# DS158-1_0-B.net
KiCad netlist of a schematic drawn in Altium Designer
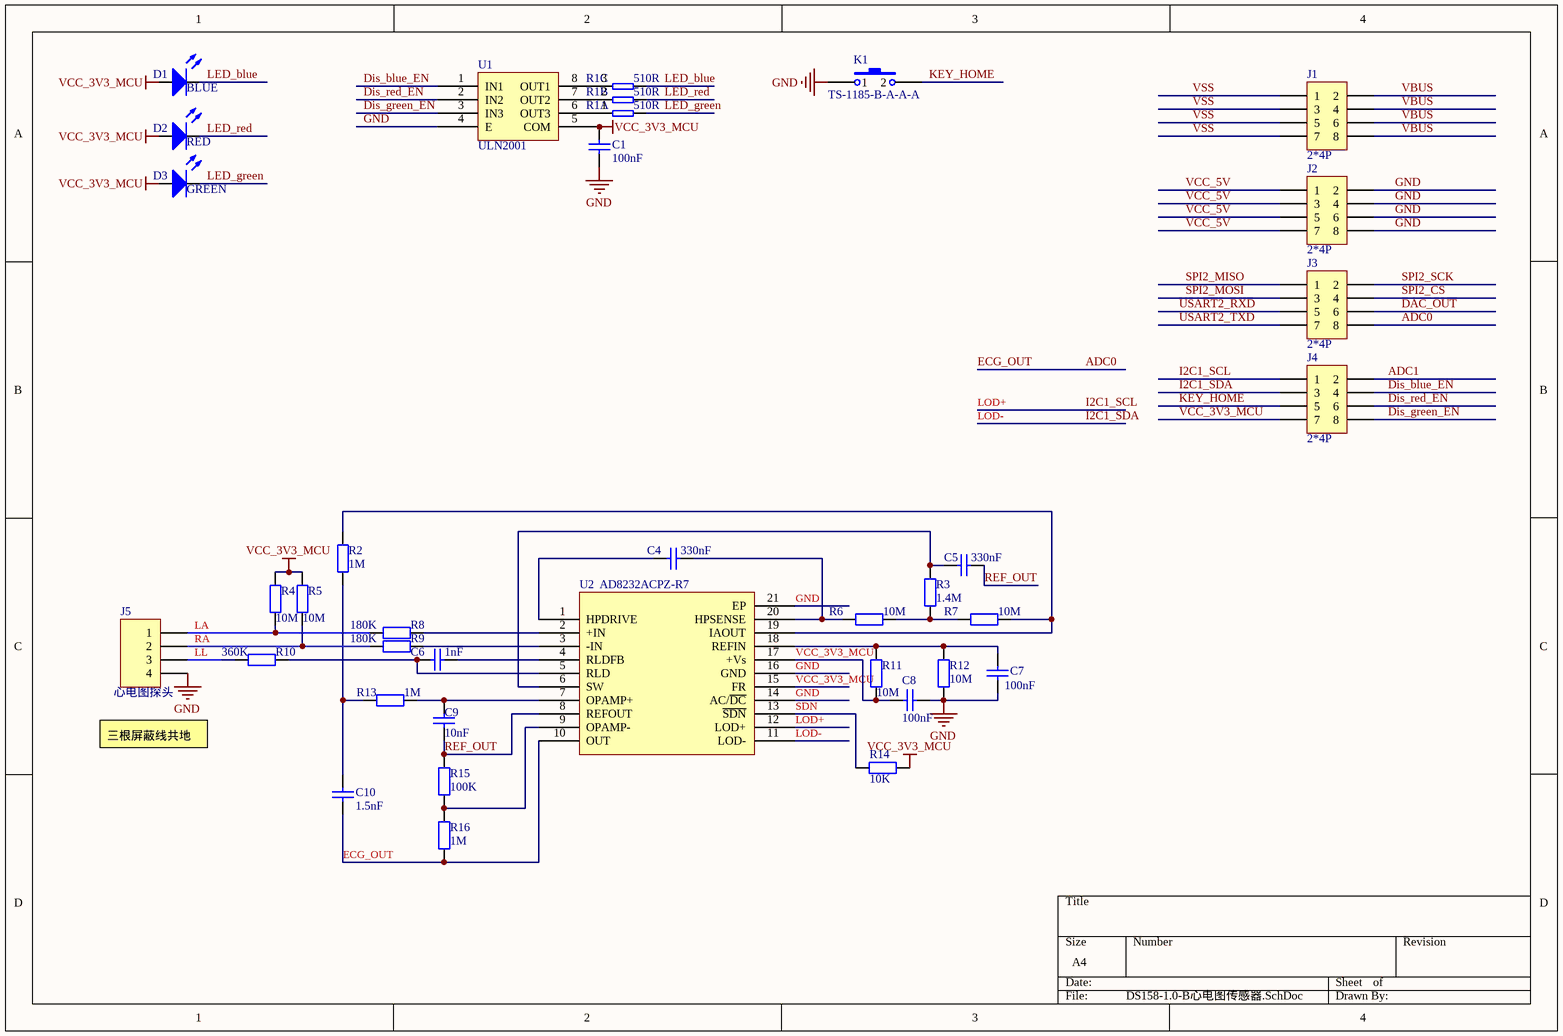
[diagram p0: DS158-1.0-B心电图传感器.SchDoc]

(export (version "E")
  (design (tool "Eeschema 10.0.6"))
  (components
    (comp (ref "C1")
      (value "100nF")
      (footprint "0603CAP")
      (description "贴片电容")
      (fields (field (name "Comment") "SMDCAP00013"))
      (libsource (lib "AD_SCH") (part "MLCC 100nF 50V ±10％ 0603"))
    )
    (comp (ref "C4")
      (value "330nF")
      (footprint "0603CAP")
      (description "贴片电容")
      (fields (field (name "Comment") "MLCC 330nF 50V ±5％ 0603"))
      (libsource (lib "AD_SCH") (part "MLCC 330nF 50V ±5％ 0603"))
    )
    (comp (ref "C5")
      (value "330nF")
      (footprint "0603CAP")
      (description "贴片电容")
      (fields (field (name "Comment") "MLCC 330nF 50V ±5％ 0603"))
      (libsource (lib "AD_SCH") (part "MLCC 330nF 50V ±5％ 0603"))
    )
    (comp (ref "C6")
      (value "1nF")
      (footprint "0603CAP")
      (description "贴片电容")
      (fields (field (name "Comment") "SMDCAP00008"))
      (libsource (lib "AD_SCH") (part "MLCC 1nF 50V ±10％ 0603"))
    )
    (comp (ref "C7")
      (value "100nF")
      (footprint "0603CAP")
      (description "贴片电容")
      (fields (field (name "Comment") "SMDCAP00013"))
      (libsource (lib "AD_SCH") (part "MLCC 100nF 50V ±10％ 0603"))
    )
    (comp (ref "C8")
      (value "100nF")
      (footprint "0603CAP")
      (description "贴片电容")
      (fields (field (name "Comment") "SMDCAP00013"))
      (libsource (lib "AD_SCH") (part "MLCC 100nF 50V ±10％ 0603"))
    )
    (comp (ref "C9")
      (value "10nF")
      (footprint "0603CAP")
      (description "贴片电容")
      (fields (field (name "Comment") "SMDCAP00010"))
      (libsource (lib "AD_SCH") (part "MLCC 10nF 50V ±10％ 0603"))
    )
    (comp (ref "C10")
      (value "1.5nF")
      (footprint "0603CAP")
      (description "贴片电容")
      (fields (field (name "Comment") "SMDCAP00008"))
      (libsource (lib "AD_SCH") (part "MLCC 1.5nF 50V ±10％ 0603"))
    )
    (comp (ref "D1")
      (value "BLUE")
      (footprint "LED_0805")
      (description "贴片LED")
      (fields (field (name "Comment") "SMDLED00010"))
      (libsource (lib "AD_SCH") (part "Chip 蓝色LED 0805"))
    )
    (comp (ref "D2")
      (value "RED")
      (footprint "LED_0805")
      (description "贴片LED")
      (fields (field (name "Comment") "SMDLED00003"))
      (libsource (lib "AD_SCH") (part "Chip 红色LED 0805"))
    )
    (comp (ref "D3")
      (value "GREEN")
      (footprint "LED_0805")
      (description "贴片LED")
      (fields (field (name "Comment") "Chip 翠绿LED 0805"))
      (libsource (lib "AD_SCH") (part "Chip 翠绿LED 0805"))
    )
    (comp (ref "J1")
      (value "2*4P")
      (footprint "X1321WVS-2x04J-C40D53")
      (description "双排针2x4P 立贴 1.27mm")
      (fields (field (name "Comment") "X1321WVS-2x04J-C40D53"))
      (libsource (lib "AD_SCH") (part "X1321WVS-2x04J-C40D53"))
    )
    (comp (ref "J2")
      (value "2*4P")
      (footprint "X1321WVS-2x04J-C40D53")
      (description "双排针2x4P 立贴 1.27mm")
      (fields (field (name "Comment") "X1321WVS-2x04J-C40D53"))
      (libsource (lib "AD_SCH") (part "X1321WVS-2x04J-C40D53"))
    )
    (comp (ref "J3")
      (value "2*4P")
      (footprint "X1321WVS-2x04J-C40D53")
      (description "双排针2x4P 立贴 1.27mm")
      (fields (field (name "Comment") "X1321WVS-2x04J-C40D53"))
      (libsource (lib "AD_SCH") (part "X1321WVS-2x04J-C40D53"))
    )
    (comp (ref "J4")
      (value "2*4P")
      (footprint "X1321WVS-2x04J-C40D53")
      (description "双排针2x4P 立贴 1.27mm")
      (fields (field (name "Comment") "X1321WVS-2x04J-C40D53"))
      (libsource (lib "AD_SCH") (part "X1321WVS-2x04J-C40D53"))
    )
    (comp (ref "J5")
      (value "心电图探头")
      (footprint "SIP4")
      (fields (field (name "Comment") "SL000000042"))
      (libsource (lib "AD_SCH") (part "DIP4 单排直针 间距2.54mm 针长11mm 铜"))
    )
    (comp (ref "K1")
      (value "TS-1185-B-A-A-A")
      (footprint "KEY_TS-1185-x-A-A-A")
      (description "轻触开关")
      (libsource (lib "AD_SCH") (part "TS-1185-B-A-A-A"))
    )
    (comp (ref "R1")
      (value "510R")
      (footprint "0603RES_Pack4")
      (description "贴片排阻")
      (fields (field (name "Comment") "SMDRES05003"))
      (libsource (lib "AD_SCH") (part "Chip R*4 510R 1/16W ±5％ 0603"))
    )
    (comp (ref "R2")
      (value "1M")
      (footprint "0603RES")
      (description "贴片电阻")
      (fields (field (name "Comment") "SMDRES00085"))
      (libsource (lib "AD_SCH") (part "Chip 1M 1/16W ±1％ 0603"))
    )
    (comp (ref "R3")
      (value "1.4M")
      (footprint "0603RES")
      (description "贴片电阻")
      (fields (field (name "Comment") "SMDRES00085"))
      (libsource (lib "AD_SCH") (part "Chip 1.4M 1/16W ±1％ 0603"))
    )
    (comp (ref "R4")
      (value "10M")
      (footprint "0603RES")
      (description "贴片电阻")
      (fields (field (name "Comment") "Chip 10M 1/16W ±1％ 0603"))
      (libsource (lib "AD_SCH") (part "Chip 10M 1/16W ±1％ 0603"))
    )
    (comp (ref "R5")
      (value "10M")
      (footprint "0603RES")
      (description "贴片电阻")
      (fields (field (name "Comment") "Chip 10M 1/16W ±1％ 0603"))
      (libsource (lib "AD_SCH") (part "Chip 10M 1/16W ±1％ 0603"))
    )
    (comp (ref "R6")
      (value "10M")
      (footprint "0603RES")
      (description "贴片电阻")
      (fields (field (name "Comment") "Chip 10M 1/16W ±1％ 0603"))
      (libsource (lib "") (part "Chip 10M 1/16W ±1％ 0603_2"))
    )
    (comp (ref "R7")
      (value "10M")
      (footprint "0603RES")
      (description "贴片电阻")
      (fields (field (name "Comment") "Chip 10M 1/16W ±1％ 0603"))
      (libsource (lib "") (part "Chip 10M 1/16W ±1％ 0603_1"))
    )
    (comp (ref "R8")
      (value "180K")
      (footprint "0603RES")
      (description "贴片电阻")
      (fields (field (name "Comment") "Chip 180K 1/16W ±1％ 0603"))
      (libsource (lib "AD_SCH") (part "Chip 180K 1/16W ±1％ 0603"))
    )
    (comp (ref "R9")
      (value "180K")
      (footprint "0603RES")
      (description "贴片电阻")
      (fields (field (name "Comment") "Chip 180K 1/16W ±1％ 0603"))
      (libsource (lib "AD_SCH") (part "Chip 180K 1/16W ±1％ 0603"))
    )
    (comp (ref "R10")
      (value "360K")
      (footprint "0603RES")
      (description "贴片电阻")
      (fields (field (name "Comment") "Chip 360K 1/16W ±1％ 0603"))
      (libsource (lib "AD_SCH") (part "Chip 360K 1/16W ±1％ 0603"))
    )
    (comp (ref "R11")
      (value "10M")
      (footprint "0603RES")
      (description "贴片电阻")
      (fields (field (name "Comment") "Chip 10M 1/16W ±1％ 0603"))
      (libsource (lib "AD_SCH") (part "Chip 10M 1/16W ±1％ 0603"))
    )
    (comp (ref "R12")
      (value "10M")
      (footprint "0603RES")
      (description "贴片电阻")
      (fields (field (name "Comment") "Chip 10M 1/16W ±1％ 0603"))
      (libsource (lib "") (part "Chip 10M 1/16W ±1％ 0603_3"))
    )
    (comp (ref "R13")
      (value "1M")
      (footprint "0603RES")
      (description "贴片电阻")
      (fields (field (name "Comment") "SMDRES00085"))
      (libsource (lib "") (part "Chip 1M 1/16W ±1％ 0603_1"))
    )
    (comp (ref "R14")
      (value "10K")
      (footprint "0603RES")
      (description "贴片电阻")
      (fields (field (name "Comment") "SMDRES00056"))
      (libsource (lib "AD_SCH") (part "Chip 10K 1/16W ±1％ 0603"))
    )
    (comp (ref "R15")
      (value "100K")
      (footprint "0603RES")
      (description "贴片电阻")
      (fields (field (name "Comment") "SMDRES00071"))
      (libsource (lib "AD_SCH") (part "Chip 100K 1/16W ±1％ 0603"))
    )
    (comp (ref "R16")
      (value "1M")
      (footprint "0603RES")
      (description "贴片电阻")
      (fields (field (name "Comment") "SMDRES00085"))
      (libsource (lib "AD_SCH") (part "Chip 1M 1/16W ±1％ 0603"))
    )
    (comp (ref "U1")
      (value "ULN2001")
      (footprint "SO-8")
      (description "电机驱动芯片")
      (fields (field (name "Comment") "SMDIC000018"))
      (libsource (lib "AD_SCH") (part "ULN2001 SOP-8"))
    )
    (comp (ref "U2")
      (value "AD8232ACPZ-R7")
      (footprint "LFCSP_WQ")
      (description "仪表放大器")
      (fields (field (name "Comment") "SMDIC000016"))
      (libsource (lib "AD_SCH") (part "AD8232ACPZ-R7"))
    )
  )
  (nets
    (net (code "1") (name "/ADC0") (class "Default")
      (node (ref "C10") (pin "2") (pinfunction "2_2") (pintype "passive"))
      (node (ref "J3") (pin "8") (pinfunction "8_8") (pintype "passive"))
      (node (ref "R16") (pin "2") (pinfunction "2_2") (pintype "passive"))
      (node (ref "U2") (pin "10") (pinfunction "OUT_10") (pintype "passive"))
    )
    (net (code "2") (name "/ADC1") (class "Default")
      (node (ref "J4") (pin "2") (pinfunction "2_2") (pintype "passive"))
    )
    (net (code "3") (name "/DAC_OUT") (class "Default")
      (node (ref "J3") (pin "6") (pinfunction "6_6") (pintype "passive"))
    )
    (net (code "4") (name "/Dis_blue_EN") (class "Default")
      (node (ref "J4") (pin "4") (pinfunction "4_4") (pintype "passive"))
      (node (ref "U1") (pin "1") (pinfunction "IN1_1") (pintype "passive"))
    )
    (net (code "5") (name "/Dis_green_EN") (class "Default")
      (node (ref "J4") (pin "8") (pinfunction "8_8") (pintype "passive"))
      (node (ref "U1") (pin "3") (pinfunction "IN3_3") (pintype "passive"))
    )
    (net (code "6") (name "/Dis_red_EN") (class "Default")
      (node (ref "J4") (pin "6") (pinfunction "6_6") (pintype "passive"))
      (node (ref "U1") (pin "2") (pinfunction "IN2_2") (pintype "passive"))
    )
    (net (code "7") (name "/I2C1_SCL") (class "Default")
      (node (ref "J4") (pin "1") (pinfunction "1_1") (pintype "passive"))
      (node (ref "U2") (pin "12") (pinfunction "LOD+_12") (pintype "passive"))
    )
    (net (code "8") (name "/I2C1_SDA") (class "Default")
      (node (ref "J4") (pin "3") (pinfunction "3_3") (pintype "passive"))
      (node (ref "U2") (pin "11") (pinfunction "LOD-_11") (pintype "passive"))
    )
    (net (code "9") (name "/KEY_HOME") (class "Default")
      (node (ref "J4") (pin "5") (pinfunction "5_5") (pintype "passive"))
      (node (ref "K1") (pin "2") (pinfunction "2_2") (pintype "passive"))
    )
    (net (code "10") (name "/LA") (class "Default")
      (node (ref "J5") (pin "1") (pinfunction "1_1") (pintype "passive"))
      (node (ref "R4") (pin "1") (pinfunction "1_1") (pintype "passive"))
      (node (ref "R8") (pin "1") (pinfunction "1_1") (pintype "passive"))
    )
    (net (code "11") (name "/LED_blue") (class "Default")
      (node (ref "D1") (pin "2") (pinfunction "K_2") (pintype "passive"))
      (node (ref "R1") (pin "6") (pinfunction "6_6") (pintype "passive"))
    )
    (net (code "12") (name "/LED_green") (class "Default")
      (node (ref "D3") (pin "2") (pinfunction "K_2") (pintype "passive"))
      (node (ref "R1") (pin "8") (pinfunction "8_8") (pintype "passive"))
    )
    (net (code "13") (name "/LED_red") (class "Default")
      (node (ref "D2") (pin "2") (pinfunction "K_2") (pintype "passive"))
      (node (ref "R1") (pin "7") (pinfunction "7_7") (pintype "passive"))
    )
    (net (code "14") (name "/LL") (class "Default")
      (node (ref "J5") (pin "3") (pinfunction "3_3") (pintype "passive"))
      (node (ref "R10") (pin "2") (pinfunction "2_2") (pintype "passive"))
    )
    (net (code "15") (name "/RA") (class "Default")
      (node (ref "J5") (pin "2") (pinfunction "2_2") (pintype "passive"))
      (node (ref "R5") (pin "1") (pinfunction "1_1") (pintype "passive"))
      (node (ref "R9") (pin "1") (pinfunction "1_1") (pintype "passive"))
    )
    (net (code "16") (name "/REF_OUT") (class "Default")
      (node (ref "C5") (pin "1") (pinfunction "1_1") (pintype "passive"))
      (node (ref "C9") (pin "2") (pinfunction "2_2") (pintype "passive"))
      (node (ref "R15") (pin "1") (pinfunction "1_1") (pintype "passive"))
      (node (ref "U2") (pin "8") (pinfunction "REFOUT_8") (pintype "passive"))
    )
    (net (code "17") (name "/SDN") (class "Default")
      (node (ref "R14") (pin "1") (pinfunction "1_1") (pintype "passive"))
      (node (ref "U2") (pin "13") (pinfunction "~{SDN}_13") (pintype "passive"))
    )
    (net (code "18") (name "/SPI2_CS") (class "Default")
      (node (ref "J3") (pin "4") (pinfunction "4_4") (pintype "passive"))
    )
    (net (code "19") (name "/SPI2_MISO") (class "Default")
      (node (ref "J3") (pin "1") (pinfunction "1_1") (pintype "passive"))
    )
    (net (code "20") (name "/SPI2_MOSI") (class "Default")
      (node (ref "J3") (pin "3") (pinfunction "3_3") (pintype "passive"))
    )
    (net (code "21") (name "/SPI2_SCK") (class "Default")
      (node (ref "J3") (pin "2") (pinfunction "2_2") (pintype "passive"))
    )
    (net (code "22") (name "/USART2_RXD") (class "Default")
      (node (ref "J3") (pin "5") (pinfunction "5_5") (pintype "passive"))
    )
    (net (code "23") (name "/USART2_TXD") (class "Default")
      (node (ref "J3") (pin "7") (pinfunction "7_7") (pintype "passive"))
    )
    (net (code "24") (name "/VBUS") (class "Default")
      (node (ref "J1") (pin "2") (pinfunction "2_2") (pintype "passive"))
      (node (ref "J1") (pin "4") (pinfunction "4_4") (pintype "passive"))
      (node (ref "J1") (pin "6") (pinfunction "6_6") (pintype "passive"))
      (node (ref "J1") (pin "8") (pinfunction "8_8") (pintype "passive"))
    )
    (net (code "25") (name "/VCC_5V") (class "Default")
      (node (ref "J2") (pin "1") (pinfunction "1_1") (pintype "passive"))
      (node (ref "J2") (pin "3") (pinfunction "3_3") (pintype "passive"))
      (node (ref "J2") (pin "5") (pinfunction "5_5") (pintype "passive"))
      (node (ref "J2") (pin "7") (pinfunction "7_7") (pintype "passive"))
    )
    (net (code "26") (name "/VSS") (class "Default")
      (node (ref "J1") (pin "1") (pinfunction "1_1") (pintype "passive"))
      (node (ref "J1") (pin "3") (pinfunction "3_3") (pintype "passive"))
      (node (ref "J1") (pin "5") (pinfunction "5_5") (pintype "passive"))
      (node (ref "J1") (pin "7") (pinfunction "7_7") (pintype "passive"))
    )
    (net (code "27") (name "GND") (class "Default")
      (node (ref "C1") (pin "1") (pinfunction "1_1") (pintype "passive"))
      (node (ref "C7") (pin "1") (pinfunction "1_1") (pintype "passive"))
      (node (ref "C8") (pin "2") (pinfunction "2_2") (pintype "passive"))
      (node (ref "J2") (pin "2") (pinfunction "2_2") (pintype "passive"))
      (node (ref "J2") (pin "4") (pinfunction "4_4") (pintype "passive"))
      (node (ref "J2") (pin "6") (pinfunction "6_6") (pintype "passive"))
      (node (ref "J2") (pin "8") (pinfunction "8_8") (pintype "passive"))
      (node (ref "J5") (pin "4") (pinfunction "4_4") (pintype "passive"))
      (node (ref "K1") (pin "1") (pinfunction "1_1") (pintype "passive"))
      (node (ref "R12") (pin "2") (pinfunction "2_2") (pintype "passive"))
      (node (ref "U1") (pin "4") (pinfunction "E_4") (pintype "passive"))
      (node (ref "U2") (pin "14") (pinfunction "AC/~{DC}_14") (pintype "passive"))
      (node (ref "U2") (pin "16") (pinfunction "GND_16") (pintype "passive"))
      (node (ref "U2") (pin "21") (pinfunction "EP_21") (pintype "passive"))
    )
    (net (code "28") (name "Net-(C10-Pad1)") (class "Default")
      (node (ref "C10") (pin "1") (pinfunction "1_1") (pintype "passive"))
      (node (ref "R13") (pin "1") (pinfunction "1_1") (pintype "passive"))
      (node (ref "R2") (pin "2") (pinfunction "2_2") (pintype "passive"))
    )
    (net (code "29") (name "Net-(R3-Pad1)") (class "Default")
      (node (ref "R3") (pin "1") (pinfunction "1_1") (pintype "passive"))
      (node (ref "R6") (pin "1") (pinfunction "1_1") (pintype "passive"))
      (node (ref "R7") (pin "1") (pinfunction "1_1") (pintype "passive"))
    )
    (net (code "30") (name "Net-(U1-OUT1)") (class "Default")
      (node (ref "R1") (pin "3") (pinfunction "3_3") (pintype "passive"))
      (node (ref "U1") (pin "8") (pinfunction "OUT1_8") (pintype "passive"))
    )
    (net (code "31") (name "Net-(U1-OUT2)") (class "Default")
      (node (ref "R1") (pin "2") (pinfunction "2_2") (pintype "passive"))
      (node (ref "U1") (pin "7") (pinfunction "OUT2_7") (pintype "passive"))
    )
    (net (code "32") (name "Net-(U1-OUT3)") (class "Default")
      (node (ref "R1") (pin "1") (pinfunction "1_1") (pintype "passive"))
      (node (ref "U1") (pin "6") (pinfunction "OUT3_6") (pintype "passive"))
    )
    (net (code "33") (name "Net-(U2-+IN)") (class "Default")
      (node (ref "R8") (pin "2") (pinfunction "2_2") (pintype "passive"))
      (node (ref "U2") (pin "2") (pinfunction "+IN_2") (pintype "passive"))
    )
    (net (code "34") (name "Net-(U2--IN)") (class "Default")
      (node (ref "R9") (pin "2") (pinfunction "2_2") (pintype "passive"))
      (node (ref "U2") (pin "3") (pinfunction "-IN_3") (pintype "passive"))
    )
    (net (code "35") (name "Net-(U2-HPDRIVE)") (class "Default")
      (node (ref "C4") (pin "1") (pinfunction "1_1") (pintype "passive"))
      (node (ref "U2") (pin "1") (pinfunction "HPDRIVE_1") (pintype "passive"))
    )
    (net (code "36") (name "Net-(U2-HPSENSE)") (class "Default")
      (node (ref "C4") (pin "2") (pinfunction "2_2") (pintype "passive"))
      (node (ref "R6") (pin "2") (pinfunction "2_2") (pintype "passive"))
      (node (ref "U2") (pin "20") (pinfunction "HPSENSE_20") (pintype "passive"))
    )
    (net (code "37") (name "Net-(U2-IAOUT)") (class "Default")
      (node (ref "R2") (pin "1") (pinfunction "1_1") (pintype "passive"))
      (node (ref "R7") (pin "2") (pinfunction "2_2") (pintype "passive"))
      (node (ref "U2") (pin "19") (pinfunction "IAOUT_19") (pintype "passive"))
    )
    (net (code "38") (name "Net-(U2-OPAMP+)") (class "Default")
      (node (ref "C9") (pin "1") (pinfunction "1_1") (pintype "passive"))
      (node (ref "R13") (pin "2") (pinfunction "2_2") (pintype "passive"))
      (node (ref "U2") (pin "7") (pinfunction "OPAMP+_7") (pintype "passive"))
    )
    (net (code "39") (name "Net-(U2-OPAMP-)") (class "Default")
      (node (ref "R15") (pin "2") (pinfunction "2_2") (pintype "passive"))
      (node (ref "R16") (pin "1") (pinfunction "1_1") (pintype "passive"))
      (node (ref "U2") (pin "9") (pinfunction "OPAMP-_9") (pintype "passive"))
    )
    (net (code "40") (name "Net-(U2-REFIN)") (class "Default")
      (node (ref "C7") (pin "2") (pinfunction "2_2") (pintype "passive"))
      (node (ref "R11") (pin "2") (pinfunction "2_2") (pintype "passive"))
      (node (ref "R12") (pin "1") (pinfunction "1_1") (pintype "passive"))
      (node (ref "U2") (pin "18") (pinfunction "REFIN_18") (pintype "passive"))
    )
    (net (code "41") (name "Net-(U2-RLD)") (class "Default")
      (node (ref "C6") (pin "1") (pinfunction "1_1") (pintype "passive"))
      (node (ref "R10") (pin "1") (pinfunction "1_1") (pintype "passive"))
      (node (ref "U2") (pin "5") (pinfunction "RLD_5") (pintype "passive"))
    )
    (net (code "42") (name "Net-(U2-RLDFB)") (class "Default")
      (node (ref "C6") (pin "2") (pinfunction "2_2") (pintype "passive"))
      (node (ref "U2") (pin "4") (pinfunction "RLDFB_4") (pintype "passive"))
    )
    (net (code "43") (name "Net-(U2-SW)") (class "Default")
      (node (ref "C5") (pin "2") (pinfunction "2_2") (pintype "passive"))
      (node (ref "R3") (pin "2") (pinfunction "2_2") (pintype "passive"))
      (node (ref "U2") (pin "6") (pinfunction "SW_6") (pintype "passive"))
    )
    (net (code "44") (name "VCC_3V3_MCU") (class "Default")
      (node (ref "C1") (pin "2") (pinfunction "2_2") (pintype "passive"))
      (node (ref "C8") (pin "1") (pinfunction "1_1") (pintype "passive"))
      (node (ref "D1") (pin "1") (pinfunction "A_1") (pintype "passive"))
      (node (ref "D2") (pin "1") (pinfunction "A_1") (pintype "passive"))
      (node (ref "D3") (pin "1") (pinfunction "A_1") (pintype "passive"))
      (node (ref "J4") (pin "7") (pinfunction "7_7") (pintype "passive"))
      (node (ref "R11") (pin "1") (pinfunction "1_1") (pintype "passive"))
      (node (ref "R14") (pin "2") (pinfunction "2_2") (pintype "passive"))
      (node (ref "R4") (pin "2") (pinfunction "2_2") (pintype "passive"))
      (node (ref "R5") (pin "2") (pinfunction "2_2") (pintype "passive"))
      (node (ref "U1") (pin "5") (pinfunction "COM_5") (pintype "passive"))
      (node (ref "U2") (pin "15") (pinfunction "FR_15") (pintype "passive"))
      (node (ref "U2") (pin "17") (pinfunction "+Vs_17") (pintype "passive"))
    )
  )
)
